# DigitalIO_3_3V_LevelShift.net
KiCad netlist of a schematic drawn in EAGLE
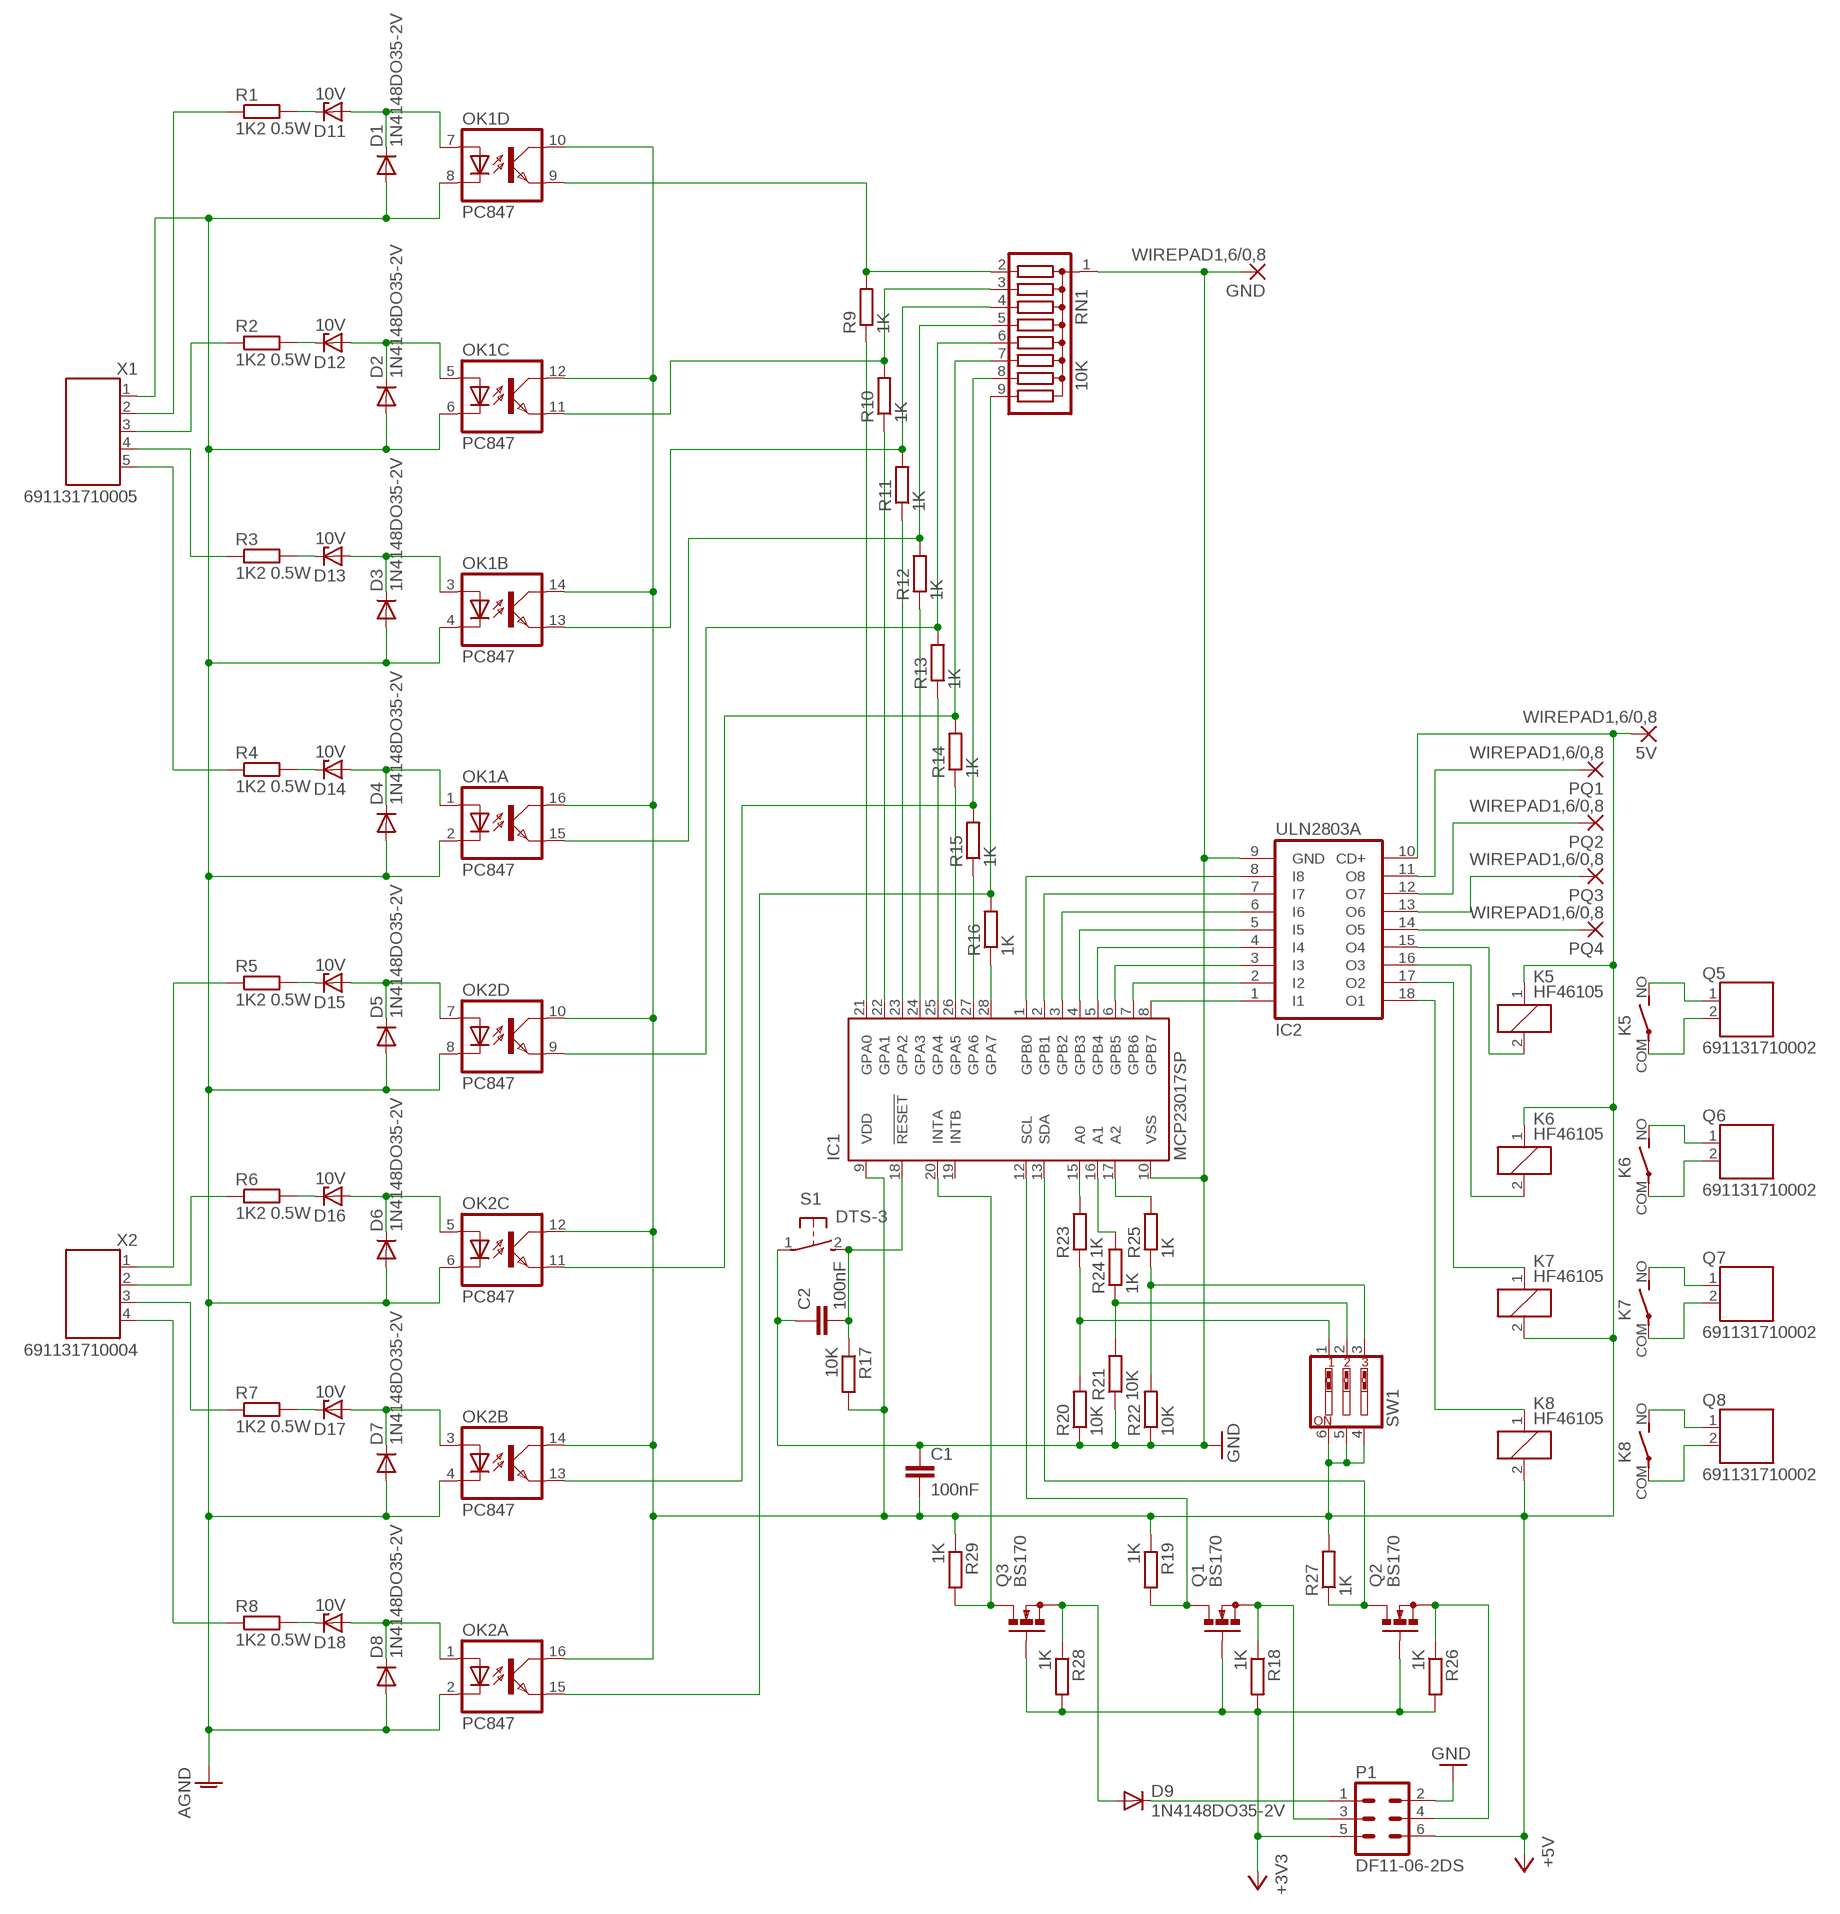
[diagram p0: schematic, sheet 1]

(export (version "E")
  (design (tool "Eeschema 10.0.6"))
  (components
    (comp (ref "5V")
      (value "WIREPAD1,6/0,8")
      (footprint "eagle-import:1,6_0,8")
      (libsource (lib "eagle-import") (part "WIREPAD1,6/0,8"))
    )
    (comp (ref "C1")
      (value "100nF")
      (footprint "eagle-import:C0805")
      (fields (field (name "MF") "MULTICOMP") (field (name "MPN") "MCRR50104X7RK0050"))
      (libsource (lib "eagle-import") (part "C-EUC0805"))
    )
    (comp (ref "C2")
      (value "100nF")
      (footprint "eagle-import:C0805")
      (fields (field (name "MF") "MULTICOMP") (field (name "MPN") "MCRR50104X7RK0050"))
      (libsource (lib "eagle-import") (part "C-EUC0805"))
    )
    (comp (ref "D1")
      (value "1N4148DO35-2V")
      (footprint "eagle-import:DO35-2V")
      (libsource (lib "eagle-import") (part "1N4148DO35-2V"))
    )
    (comp (ref "D2")
      (value "1N4148DO35-2V")
      (footprint "eagle-import:DO35-2V")
      (libsource (lib "eagle-import") (part "1N4148DO35-2V"))
    )
    (comp (ref "D3")
      (value "1N4148DO35-2V")
      (footprint "eagle-import:DO35-2V")
      (libsource (lib "eagle-import") (part "1N4148DO35-2V"))
    )
    (comp (ref "D4")
      (value "1N4148DO35-2V")
      (footprint "eagle-import:DO35-2V")
      (libsource (lib "eagle-import") (part "1N4148DO35-2V"))
    )
    (comp (ref "D5")
      (value "1N4148DO35-2V")
      (footprint "eagle-import:DO35-2V")
      (libsource (lib "eagle-import") (part "1N4148DO35-2V"))
    )
    (comp (ref "D6")
      (value "1N4148DO35-2V")
      (footprint "eagle-import:DO35-2V")
      (libsource (lib "eagle-import") (part "1N4148DO35-2V"))
    )
    (comp (ref "D7")
      (value "1N4148DO35-2V")
      (footprint "eagle-import:DO35-2V")
      (libsource (lib "eagle-import") (part "1N4148DO35-2V"))
    )
    (comp (ref "D8")
      (value "1N4148DO35-2V")
      (footprint "eagle-import:DO35-2V")
      (libsource (lib "eagle-import") (part "1N4148DO35-2V"))
    )
    (comp (ref "D9")
      (value "1N4148DO35-2V")
      (footprint "eagle-import:DO35-2V")
      (libsource (lib "eagle-import") (part "1N4148DO35-2V"))
    )
    (comp (ref "D11")
      (value "10V")
      (footprint "eagle-import:ZDIO-2.5")
      (libsource (lib "eagle-import") (part "ZENER-DIODEZD-2.5"))
    )
    (comp (ref "D12")
      (value "10V")
      (footprint "eagle-import:ZDIO-2.5")
      (libsource (lib "eagle-import") (part "ZENER-DIODEZD-2.5"))
    )
    (comp (ref "D13")
      (value "10V")
      (footprint "eagle-import:ZDIO-2.5")
      (libsource (lib "eagle-import") (part "ZENER-DIODEZD-2.5"))
    )
    (comp (ref "D14")
      (value "10V")
      (footprint "eagle-import:ZDIO-2.5")
      (libsource (lib "eagle-import") (part "ZENER-DIODEZD-2.5"))
    )
    (comp (ref "D15")
      (value "10V")
      (footprint "eagle-import:ZDIO-2.5")
      (libsource (lib "eagle-import") (part "ZENER-DIODEZD-2.5"))
    )
    (comp (ref "D16")
      (value "10V")
      (footprint "eagle-import:ZDIO-2.5")
      (libsource (lib "eagle-import") (part "ZENER-DIODEZD-2.5"))
    )
    (comp (ref "D17")
      (value "10V")
      (footprint "eagle-import:ZDIO-2.5")
      (libsource (lib "eagle-import") (part "ZENER-DIODEZD-2.5"))
    )
    (comp (ref "D18")
      (value "10V")
      (footprint "eagle-import:ZDIO-2.5")
      (libsource (lib "eagle-import") (part "ZENER-DIODEZD-2.5"))
    )
    (comp (ref "GND")
      (value "WIREPAD1,6/0,8")
      (footprint "eagle-import:1,6_0,8")
      (libsource (lib "eagle-import") (part "WIREPAD1,6/0,8"))
    )
    (comp (ref "IC1")
      (value "MCP23017SP")
      (footprint "eagle-import:DIL28-3")
      (libsource (lib "eagle-import") (part "MCP23017SP"))
    )
    (comp (ref "IC2")
      (value "ULN2803A")
      (footprint "eagle-import:DIL18")
      (fields (field (name "MF") "STMICROELECTRONICS"))
      (libsource (lib "eagle-import") (part "ULN2803A"))
    )
    (comp (ref "K5")
      (value "HF46105")
      (footprint "eagle-import:HF46")
      (libsource (lib "eagle-import") (part "HF46?105"))
    )
    (comp (ref "K6")
      (value "HF46105")
      (footprint "eagle-import:HF46")
      (libsource (lib "eagle-import") (part "HF46?105"))
    )
    (comp (ref "K7")
      (value "HF46105")
      (footprint "eagle-import:HF46")
      (libsource (lib "eagle-import") (part "HF46?105"))
    )
    (comp (ref "K8")
      (value "HF46105")
      (footprint "eagle-import:HF46")
      (libsource (lib "eagle-import") (part "HF46?105"))
    )
    (comp (ref "OK1")
      (value "PC847")
      (footprint "eagle-import:DIL16")
      (libsource (lib "eagle-import") (part "PC847"))
    )
    (comp (ref "OK2")
      (value "PC847")
      (footprint "eagle-import:DIL16")
      (libsource (lib "eagle-import") (part "PC847"))
    )
    (comp (ref "P1")
      (value "DF11-06-2DS")
      (footprint "eagle-import:DF11-06DP-2DS")
      (libsource (lib "eagle-import") (part "DF11-06-2DS"))
    )
    (comp (ref "PQ1")
      (value "WIREPAD1,6/0,8")
      (footprint "eagle-import:1,6_0,8")
      (libsource (lib "eagle-import") (part "WIREPAD1,6/0,8"))
    )
    (comp (ref "PQ2")
      (value "WIREPAD1,6/0,8")
      (footprint "eagle-import:1,6_0,8")
      (libsource (lib "eagle-import") (part "WIREPAD1,6/0,8"))
    )
    (comp (ref "PQ3")
      (value "WIREPAD1,6/0,8")
      (footprint "eagle-import:1,6_0,8")
      (libsource (lib "eagle-import") (part "WIREPAD1,6/0,8"))
    )
    (comp (ref "PQ4")
      (value "WIREPAD1,6/0,8")
      (footprint "eagle-import:1,6_0,8")
      (libsource (lib "eagle-import") (part "WIREPAD1,6/0,8"))
    )
    (comp (ref "Q1")
      (value "BS170")
      (footprint "eagle-import:SOT54E")
      (fields (field (name "MF") "ON SEMICONDUCTOR") (field (name "MPN") "BS170G"))
      (libsource (lib "eagle-import") (part "BS170"))
    )
    (comp (ref "Q2")
      (value "BS170")
      (footprint "eagle-import:SOT54E")
      (fields (field (name "MF") "ON SEMICONDUCTOR") (field (name "MPN") "BS170G"))
      (libsource (lib "eagle-import") (part "BS170"))
    )
    (comp (ref "Q3")
      (value "BS170")
      (footprint "eagle-import:SOT54E")
      (fields (field (name "MF") "ON SEMICONDUCTOR") (field (name "MPN") "BS170G"))
      (libsource (lib "eagle-import") (part "BS170"))
    )
    (comp (ref "Q5")
      (value "691131710002")
      (footprint "eagle-import:691131710002")
      (libsource (lib "eagle-import") (part "691131710002"))
    )
    (comp (ref "Q6")
      (value "691131710002")
      (footprint "eagle-import:691131710002")
      (libsource (lib "eagle-import") (part "691131710002"))
    )
    (comp (ref "Q7")
      (value "691131710002")
      (footprint "eagle-import:691131710002")
      (libsource (lib "eagle-import") (part "691131710002"))
    )
    (comp (ref "Q8")
      (value "691131710002")
      (footprint "eagle-import:691131710002")
      (libsource (lib "eagle-import") (part "691131710002"))
    )
    (comp (ref "R1")
      (value "1K2 0.5W")
      (footprint "eagle-import:0207_2V")
      (fields (field (name "MF") "MULTICOMP") (field (name "MPN") "MCF 0.25W 1K2"))
      (libsource (lib "eagle-import") (part "resistor_R-EU_0207/2V"))
    )
    (comp (ref "R2")
      (value "1K2 0.5W")
      (footprint "eagle-import:0207_2V")
      (fields (field (name "MF") "MULTICOMP") (field (name "MPN") "MCF 0.25W 1K2"))
      (libsource (lib "eagle-import") (part "resistor_R-EU_0207/2V"))
    )
    (comp (ref "R3")
      (value "1K2 0.5W")
      (footprint "eagle-import:0207_2V")
      (fields (field (name "MF") "MULTICOMP") (field (name "MPN") "MCF 0.25W 1K2"))
      (libsource (lib "eagle-import") (part "resistor_R-EU_0207/2V"))
    )
    (comp (ref "R4")
      (value "1K2 0.5W")
      (footprint "eagle-import:0207_2V")
      (fields (field (name "MF") "MULTICOMP") (field (name "MPN") "MCF 0.25W 1K2"))
      (libsource (lib "eagle-import") (part "resistor_R-EU_0207/2V"))
    )
    (comp (ref "R5")
      (value "1K2 0.5W")
      (footprint "eagle-import:0207_2V")
      (fields (field (name "MF") "MULTICOMP") (field (name "MPN") "MCF 0.25W 1K2"))
      (libsource (lib "eagle-import") (part "resistor_R-EU_0207/2V"))
    )
    (comp (ref "R6")
      (value "1K2 0.5W")
      (footprint "eagle-import:0207_2V")
      (fields (field (name "MF") "MULTICOMP") (field (name "MPN") "MCF 0.25W 1K2"))
      (libsource (lib "eagle-import") (part "resistor_R-EU_0207/2V"))
    )
    (comp (ref "R7")
      (value "1K2 0.5W")
      (footprint "eagle-import:0207_2V")
      (fields (field (name "MF") "MULTICOMP") (field (name "MPN") "MCF 0.25W 1K2"))
      (libsource (lib "eagle-import") (part "resistor_R-EU_0207/2V"))
    )
    (comp (ref "R8")
      (value "1K2 0.5W")
      (footprint "eagle-import:0207_2V")
      (fields (field (name "MF") "MULTICOMP") (field (name "MPN") "MCF 0.25W 1K2"))
      (libsource (lib "eagle-import") (part "resistor_R-EU_0207/2V"))
    )
    (comp (ref "R9")
      (value "1K")
      (footprint "eagle-import:0204V")
      (libsource (lib "eagle-import") (part "resistor_R-EU_0204/2V"))
    )
    (comp (ref "R10")
      (value "1K")
      (footprint "eagle-import:0204V")
      (libsource (lib "eagle-import") (part "resistor_R-EU_0204/2V"))
    )
    (comp (ref "R11")
      (value "1K")
      (footprint "eagle-import:0204V")
      (libsource (lib "eagle-import") (part "resistor_R-EU_0204/2V"))
    )
    (comp (ref "R12")
      (value "1K")
      (footprint "eagle-import:0204V")
      (libsource (lib "eagle-import") (part "resistor_R-EU_0204/2V"))
    )
    (comp (ref "R13")
      (value "1K")
      (footprint "eagle-import:0204V")
      (libsource (lib "eagle-import") (part "resistor_R-EU_0204/2V"))
    )
    (comp (ref "R14")
      (value "1K")
      (footprint "eagle-import:0204V")
      (libsource (lib "eagle-import") (part "resistor_R-EU_0204/2V"))
    )
    (comp (ref "R15")
      (value "1K")
      (footprint "eagle-import:0204V")
      (libsource (lib "eagle-import") (part "resistor_R-EU_0204/2V"))
    )
    (comp (ref "R16")
      (value "1K")
      (footprint "eagle-import:0204V")
      (libsource (lib "eagle-import") (part "resistor_R-EU_0204/2V"))
    )
    (comp (ref "R17")
      (value "10K")
      (footprint "eagle-import:0204V")
      (libsource (lib "eagle-import") (part "resistor_R-EU_0204/2V"))
    )
    (comp (ref "R18")
      (value "1K")
      (footprint "eagle-import:0204V")
      (libsource (lib "eagle-import") (part "R-EU_0204/2V"))
    )
    (comp (ref "R19")
      (value "1K")
      (footprint "eagle-import:0204V")
      (libsource (lib "eagle-import") (part "R-EU_0204/2V"))
    )
    (comp (ref "R20")
      (value "10K")
      (footprint "eagle-import:0204V")
      (libsource (lib "eagle-import") (part "resistor_R-EU_0204/2V"))
    )
    (comp (ref "R21")
      (value "10K")
      (footprint "eagle-import:0204V")
      (libsource (lib "eagle-import") (part "resistor_R-EU_0204/2V"))
    )
    (comp (ref "R22")
      (value "10K")
      (footprint "eagle-import:0204V")
      (libsource (lib "eagle-import") (part "resistor_R-EU_0204/2V"))
    )
    (comp (ref "R23")
      (value "1K")
      (footprint "eagle-import:0204V")
      (libsource (lib "eagle-import") (part "resistor_R-EU_0204/2V"))
    )
    (comp (ref "R24")
      (value "1K")
      (footprint "eagle-import:0204V")
      (libsource (lib "eagle-import") (part "resistor_R-EU_0204/2V"))
    )
    (comp (ref "R25")
      (value "1K")
      (footprint "eagle-import:0204V")
      (libsource (lib "eagle-import") (part "resistor_R-EU_0204/2V"))
    )
    (comp (ref "R26")
      (value "1K")
      (footprint "eagle-import:0204V")
      (libsource (lib "eagle-import") (part "R-EU_0204/2V"))
    )
    (comp (ref "R27")
      (value "1K")
      (footprint "eagle-import:0204V")
      (libsource (lib "eagle-import") (part "R-EU_0204/2V"))
    )
    (comp (ref "R28")
      (value "1K")
      (footprint "eagle-import:0204V")
      (libsource (lib "eagle-import") (part "R-EU_0204/2V"))
    )
    (comp (ref "R29")
      (value "1K")
      (footprint "eagle-import:0204V")
      (libsource (lib "eagle-import") (part "R-EU_0204/2V"))
    )
    (comp (ref "RN1")
      (value "10K")
      (footprint "eagle-import:SIL9")
      (libsource (lib "eagle-import") (part "G08R"))
    )
    (comp (ref "S1")
      (value "DTS-3")
      (footprint "eagle-import:DTS-3")
      (libsource (lib "eagle-import") (part "DTS-3"))
    )
    (comp (ref "SW1")
      (value "SW_DIP-3")
      (footprint "eagle-import:EDG-03")
      (libsource (lib "eagle-import") (part "SW_DIP-3"))
    )
    (comp (ref "X1")
      (value "691131710005")
      (footprint "eagle-import:691131710005")
      (libsource (lib "eagle-import") (part "691131710005"))
    )
    (comp (ref "X2")
      (value "691131710004")
      (footprint "eagle-import:691131710004")
      (libsource (lib "eagle-import") (part "691131710004"))
    )
  )
  (nets
    (net (code "1") (name "+3V3") (class "Default")
      (node (ref "P1") (pin "5") (pinfunction "5_5") (pintype "passive"))
      (node (ref "Q1") (pin "G") (pinfunction "G_G") (pintype "passive"))
      (node (ref "Q2") (pin "G") (pinfunction "G_G") (pintype "passive"))
      (node (ref "Q3") (pin "G") (pinfunction "G_G") (pintype "passive"))
      (node (ref "R18") (pin "2") (pinfunction "2_2") (pintype "passive"))
      (node (ref "R26") (pin "2") (pinfunction "2_2") (pintype "passive"))
      (node (ref "R28") (pin "2") (pinfunction "2_2") (pintype "passive"))
    )
    (net (code "2") (name "+5V") (class "Default")
      (node (ref "5V") (pin "1") (pinfunction "P_1") (pintype "passive"))
      (node (ref "C1") (pin "2") (pinfunction "2_2") (pintype "passive"))
      (node (ref "IC1") (pin "9") (pinfunction "VDD_9") (pintype "power_in"))
      (node (ref "IC2") (pin "10") (pinfunction "CD+_10") (pintype "passive"))
      (node (ref "K5") (pin "1") (pinfunction "1_1") (pintype "passive"))
      (node (ref "K6") (pin "1") (pinfunction "1_1") (pintype "passive"))
      (node (ref "K7") (pin "2") (pinfunction "2_2") (pintype "passive"))
      (node (ref "K8") (pin "2") (pinfunction "2_2") (pintype "passive"))
      (node (ref "OK1") (pin "10") (pinfunction "COL_10") (pintype "passive"))
      (node (ref "OK1") (pin "12") (pinfunction "COL_12") (pintype "passive"))
      (node (ref "OK1") (pin "14") (pinfunction "COL_14") (pintype "passive"))
      (node (ref "OK1") (pin "16") (pinfunction "COL_16") (pintype "passive"))
      (node (ref "OK2") (pin "10") (pinfunction "COL_10") (pintype "passive"))
      (node (ref "OK2") (pin "12") (pinfunction "COL_12") (pintype "passive"))
      (node (ref "OK2") (pin "14") (pinfunction "COL_14") (pintype "passive"))
      (node (ref "OK2") (pin "16") (pinfunction "COL_16") (pintype "passive"))
      (node (ref "P1") (pin "6") (pinfunction "6_6") (pintype "passive"))
      (node (ref "R17") (pin "2") (pinfunction "2_2") (pintype "passive"))
      (node (ref "R19") (pin "1") (pinfunction "1_1") (pintype "passive"))
      (node (ref "R27") (pin "2") (pinfunction "2_2") (pintype "passive"))
      (node (ref "R29") (pin "1") (pinfunction "1_1") (pintype "passive"))
      (node (ref "SW1") (pin "4") (pinfunction "4_4") (pintype "passive"))
      (node (ref "SW1") (pin "5") (pinfunction "5_5") (pintype "passive"))
      (node (ref "SW1") (pin "6") (pinfunction "6_6") (pintype "passive"))
    )
    (net (code "3") (name "AGND") (class "Default")
      (node (ref "D1") (pin "A") (pinfunction "A_A") (pintype "passive"))
      (node (ref "D2") (pin "A") (pinfunction "A_A") (pintype "passive"))
      (node (ref "D3") (pin "A") (pinfunction "A_A") (pintype "passive"))
      (node (ref "D4") (pin "A") (pinfunction "A_A") (pintype "passive"))
      (node (ref "D5") (pin "A") (pinfunction "A_A") (pintype "passive"))
      (node (ref "D6") (pin "A") (pinfunction "A_A") (pintype "passive"))
      (node (ref "D7") (pin "A") (pinfunction "A_A") (pintype "passive"))
      (node (ref "D8") (pin "A") (pinfunction "A_A") (pintype "passive"))
      (node (ref "OK1") (pin "2") (pinfunction "C_2") (pintype "passive"))
      (node (ref "OK1") (pin "4") (pinfunction "C_4") (pintype "passive"))
      (node (ref "OK1") (pin "6") (pinfunction "C_6") (pintype "passive"))
      (node (ref "OK1") (pin "8") (pinfunction "C_8") (pintype "passive"))
      (node (ref "OK2") (pin "2") (pinfunction "C_2") (pintype "passive"))
      (node (ref "OK2") (pin "4") (pinfunction "C_4") (pintype "passive"))
      (node (ref "OK2") (pin "6") (pinfunction "C_6") (pintype "passive"))
      (node (ref "OK2") (pin "8") (pinfunction "C_8") (pintype "passive"))
      (node (ref "X1") (pin "1") (pinfunction "1_1") (pintype "passive"))
    )
    (net (code "4") (name "GND") (class "Default")
      (node (ref "C1") (pin "1") (pinfunction "1_1") (pintype "passive"))
      (node (ref "C2") (pin "1") (pinfunction "1_1") (pintype "passive"))
      (node (ref "GND") (pin "1") (pinfunction "P_1") (pintype "passive"))
      (node (ref "IC1") (pin "10") (pinfunction "VSS_10") (pintype "power_in"))
      (node (ref "IC2") (pin "9") (pinfunction "GND_9") (pintype "power_in"))
      (node (ref "P1") (pin "2") (pinfunction "2_2") (pintype "passive"))
      (node (ref "R20") (pin "1") (pinfunction "1_1") (pintype "passive"))
      (node (ref "R21") (pin "1") (pinfunction "1_1") (pintype "passive"))
      (node (ref "R22") (pin "1") (pinfunction "1_1") (pintype "passive"))
      (node (ref "RN1") (pin "1") (pinfunction "1_1") (pintype "passive"))
      (node (ref "S1") (pin "1") (pinfunction "1_1") (pintype "passive"))
    )
    (net (code "5") (name "Net-(D9-PadA)") (class "Default")
      (node (ref "D9") (pin "A") (pinfunction "A_A") (pintype "passive"))
      (node (ref "Q3") (pin "S") (pinfunction "S_S") (pintype "passive"))
      (node (ref "R28") (pin "1") (pinfunction "1_1") (pintype "passive"))
    )
    (net (code "6") (name "Net-(D9-PadC)") (class "Default")
      (node (ref "D9") (pin "C") (pinfunction "C_C") (pintype "passive"))
      (node (ref "P1") (pin "1") (pinfunction "1_1") (pintype "passive"))
    )
    (net (code "7") (name "Net-(D11-PadC)") (class "Default")
      (node (ref "D11") (pin "C") (pinfunction "C_C") (pintype "passive"))
      (node (ref "R1") (pin "2") (pinfunction "2_2") (pintype "passive"))
    )
    (net (code "8") (name "Net-(D12-PadC)") (class "Default")
      (node (ref "D12") (pin "C") (pinfunction "C_C") (pintype "passive"))
      (node (ref "R2") (pin "2") (pinfunction "2_2") (pintype "passive"))
    )
    (net (code "9") (name "Net-(D13-PadC)") (class "Default")
      (node (ref "D13") (pin "C") (pinfunction "C_C") (pintype "passive"))
      (node (ref "R3") (pin "2") (pinfunction "2_2") (pintype "passive"))
    )
    (net (code "10") (name "Net-(D14-PadC)") (class "Default")
      (node (ref "D14") (pin "C") (pinfunction "C_C") (pintype "passive"))
      (node (ref "R4") (pin "2") (pinfunction "2_2") (pintype "passive"))
    )
    (net (code "11") (name "Net-(D15-PadC)") (class "Default")
      (node (ref "D15") (pin "C") (pinfunction "C_C") (pintype "passive"))
      (node (ref "R5") (pin "2") (pinfunction "2_2") (pintype "passive"))
    )
    (net (code "12") (name "Net-(D16-PadC)") (class "Default")
      (node (ref "D16") (pin "C") (pinfunction "C_C") (pintype "passive"))
      (node (ref "R6") (pin "2") (pinfunction "2_2") (pintype "passive"))
    )
    (net (code "13") (name "Net-(D17-PadC)") (class "Default")
      (node (ref "D17") (pin "C") (pinfunction "C_C") (pintype "passive"))
      (node (ref "R7") (pin "2") (pinfunction "2_2") (pintype "passive"))
    )
    (net (code "14") (name "Net-(D18-PadC)") (class "Default")
      (node (ref "D18") (pin "C") (pinfunction "C_C") (pintype "passive"))
      (node (ref "R8") (pin "2") (pinfunction "2_2") (pintype "passive"))
    )
    (net (code "15") (name "Net-(IC1-A0)") (class "Default")
      (node (ref "IC1") (pin "15") (pinfunction "A0_15") (pintype "input"))
      (node (ref "R23") (pin "2") (pinfunction "2_2") (pintype "passive"))
    )
    (net (code "16") (name "Net-(IC1-A1)") (class "Default")
      (node (ref "IC1") (pin "16") (pinfunction "A1_16") (pintype "input"))
      (node (ref "R24") (pin "2") (pinfunction "2_2") (pintype "passive"))
    )
    (net (code "17") (name "Net-(IC1-A2)") (class "Default")
      (node (ref "IC1") (pin "17") (pinfunction "A2_17") (pintype "input"))
      (node (ref "R25") (pin "2") (pinfunction "2_2") (pintype "passive"))
    )
    (net (code "18") (name "Net-(IC1-GPA0)") (class "Default")
      (node (ref "IC1") (pin "21") (pinfunction "GPA0_21") (pintype "bidirectional"))
      (node (ref "R9") (pin "1") (pinfunction "1_1") (pintype "passive"))
    )
    (net (code "19") (name "Net-(IC1-GPA1)") (class "Default")
      (node (ref "IC1") (pin "22") (pinfunction "GPA1_22") (pintype "bidirectional"))
      (node (ref "R10") (pin "1") (pinfunction "1_1") (pintype "passive"))
    )
    (net (code "20") (name "Net-(IC1-GPA2)") (class "Default")
      (node (ref "IC1") (pin "23") (pinfunction "GPA2_23") (pintype "bidirectional"))
      (node (ref "R11") (pin "1") (pinfunction "1_1") (pintype "passive"))
    )
    (net (code "21") (name "Net-(IC1-GPA3)") (class "Default")
      (node (ref "IC1") (pin "24") (pinfunction "GPA3_24") (pintype "bidirectional"))
      (node (ref "R12") (pin "1") (pinfunction "1_1") (pintype "passive"))
    )
    (net (code "22") (name "Net-(IC1-GPA4)") (class "Default")
      (node (ref "IC1") (pin "25") (pinfunction "GPA4_25") (pintype "bidirectional"))
      (node (ref "R13") (pin "1") (pinfunction "1_1") (pintype "passive"))
    )
    (net (code "23") (name "Net-(IC1-GPA5)") (class "Default")
      (node (ref "IC1") (pin "26") (pinfunction "GPA5_26") (pintype "bidirectional"))
      (node (ref "R14") (pin "1") (pinfunction "1_1") (pintype "passive"))
    )
    (net (code "24") (name "Net-(IC1-GPA6)") (class "Default")
      (node (ref "IC1") (pin "27") (pinfunction "GPA6_27") (pintype "bidirectional"))
      (node (ref "R15") (pin "1") (pinfunction "1_1") (pintype "passive"))
    )
    (net (code "25") (name "Net-(IC1-GPA7)") (class "Default")
      (node (ref "IC1") (pin "28") (pinfunction "GPA7_28") (pintype "bidirectional"))
      (node (ref "R16") (pin "1") (pinfunction "1_1") (pintype "passive"))
    )
    (net (code "26") (name "Net-(IC1-GPB0)") (class "Default")
      (node (ref "IC1") (pin "1") (pinfunction "GPB0_1") (pintype "bidirectional"))
      (node (ref "IC2") (pin "8") (pinfunction "I8_8") (pintype "input"))
    )
    (net (code "27") (name "Net-(IC1-GPB1)") (class "Default")
      (node (ref "IC1") (pin "2") (pinfunction "GPB1_2") (pintype "bidirectional"))
      (node (ref "IC2") (pin "7") (pinfunction "I7_7") (pintype "input"))
    )
    (net (code "28") (name "Net-(IC1-GPB2)") (class "Default")
      (node (ref "IC1") (pin "3") (pinfunction "GPB2_3") (pintype "bidirectional"))
      (node (ref "IC2") (pin "6") (pinfunction "I6_6") (pintype "input"))
    )
    (net (code "29") (name "Net-(IC1-GPB3)") (class "Default")
      (node (ref "IC1") (pin "4") (pinfunction "GPB3_4") (pintype "bidirectional"))
      (node (ref "IC2") (pin "5") (pinfunction "I5_5") (pintype "input"))
    )
    (net (code "30") (name "Net-(IC1-GPB4)") (class "Default")
      (node (ref "IC1") (pin "5") (pinfunction "GPB4_5") (pintype "bidirectional"))
      (node (ref "IC2") (pin "4") (pinfunction "I4_4") (pintype "input"))
    )
    (net (code "31") (name "Net-(IC1-GPB5)") (class "Default")
      (node (ref "IC1") (pin "6") (pinfunction "GPB5_6") (pintype "bidirectional"))
      (node (ref "IC2") (pin "3") (pinfunction "I3_3") (pintype "input"))
    )
    (net (code "32") (name "Net-(IC1-GPB6)") (class "Default")
      (node (ref "IC1") (pin "7") (pinfunction "GPB6_7") (pintype "bidirectional"))
      (node (ref "IC2") (pin "2") (pinfunction "I2_2") (pintype "input"))
    )
    (net (code "33") (name "Net-(IC1-GPB7)") (class "Default")
      (node (ref "IC1") (pin "8") (pinfunction "GPB7_8") (pintype "bidirectional"))
      (node (ref "IC2") (pin "1") (pinfunction "I1_1") (pintype "input"))
    )
    (net (code "34") (name "Net-(IC1-INTA)") (class "Default")
      (node (ref "IC1") (pin "20") (pinfunction "INTA_20") (pintype "output"))
      (node (ref "Q3") (pin "D") (pinfunction "D_D") (pintype "passive"))
      (node (ref "R29") (pin "2") (pinfunction "2_2") (pintype "passive"))
    )
    (net (code "35") (name "Net-(IC1-SCL)") (class "Default")
      (node (ref "IC1") (pin "12") (pinfunction "SCL_12") (pintype "input"))
      (node (ref "Q1") (pin "D") (pinfunction "D_D") (pintype "passive"))
      (node (ref "R19") (pin "2") (pinfunction "2_2") (pintype "passive"))
    )
    (net (code "36") (name "Net-(IC1-SDA)") (class "Default")
      (node (ref "IC1") (pin "13") (pinfunction "SDA_13") (pintype "bidirectional"))
      (node (ref "Q2") (pin "D") (pinfunction "D_D") (pintype "passive"))
      (node (ref "R27") (pin "1") (pinfunction "1_1") (pintype "passive"))
    )
    (net (code "37") (name "Net-(IC1-~{RESET})") (class "Default")
      (node (ref "C2") (pin "2") (pinfunction "2_2") (pintype "passive"))
      (node (ref "IC1") (pin "18") (pinfunction "~{RESET}_18") (pintype "input"))
      (node (ref "R17") (pin "1") (pinfunction "1_1") (pintype "passive"))
      (node (ref "S1") (pin "2") (pinfunction "2_2") (pintype "passive"))
    )
    (net (code "38") (name "Net-(IC2-O1)") (class "Default")
      (node (ref "IC2") (pin "18") (pinfunction "O1_18") (pintype "open_collector"))
      (node (ref "K8") (pin "1") (pinfunction "1_1") (pintype "passive"))
    )
    (net (code "39") (name "Net-(IC2-O2)") (class "Default")
      (node (ref "IC2") (pin "17") (pinfunction "O2_17") (pintype "open_collector"))
      (node (ref "K7") (pin "1") (pinfunction "1_1") (pintype "passive"))
    )
    (net (code "40") (name "Net-(IC2-O3)") (class "Default")
      (node (ref "IC2") (pin "16") (pinfunction "O3_16") (pintype "open_collector"))
      (node (ref "K6") (pin "2") (pinfunction "2_2") (pintype "passive"))
    )
    (net (code "41") (name "Net-(IC2-O4)") (class "Default")
      (node (ref "IC2") (pin "15") (pinfunction "O4_15") (pintype "open_collector"))
      (node (ref "K5") (pin "2") (pinfunction "2_2") (pintype "passive"))
    )
    (net (code "42") (name "Net-(IC2-O5)") (class "Default")
      (node (ref "IC2") (pin "14") (pinfunction "O5_14") (pintype "open_collector"))
      (node (ref "PQ4") (pin "1") (pinfunction "P_1") (pintype "passive"))
    )
    (net (code "43") (name "Net-(IC2-O6)") (class "Default")
      (node (ref "IC2") (pin "13") (pinfunction "O6_13") (pintype "open_collector"))
      (node (ref "PQ3") (pin "1") (pinfunction "P_1") (pintype "passive"))
    )
    (net (code "44") (name "Net-(IC2-O7)") (class "Default")
      (node (ref "IC2") (pin "12") (pinfunction "O7_12") (pintype "open_collector"))
      (node (ref "PQ2") (pin "1") (pinfunction "P_1") (pintype "passive"))
    )
    (net (code "45") (name "Net-(IC2-O8)") (class "Default")
      (node (ref "IC2") (pin "11") (pinfunction "O8_11") (pintype "open_collector"))
      (node (ref "PQ1") (pin "1") (pinfunction "P_1") (pintype "passive"))
    )
    (net (code "46") (name "Net-(K5B-P)") (class "Default")
      (node (ref "K5") (pin "COM") (pinfunction "P_COM") (pintype "passive"))
      (node (ref "Q5") (pin "2") (pinfunction "2_2") (pintype "passive"))
    )
    (net (code "47") (name "Net-(K5B-S)") (class "Default")
      (node (ref "K5") (pin "NO") (pinfunction "S_NO") (pintype "passive"))
      (node (ref "Q5") (pin "1") (pinfunction "1_1") (pintype "passive"))
    )
    (net (code "48") (name "Net-(K6B-P)") (class "Default")
      (node (ref "K6") (pin "COM") (pinfunction "P_COM") (pintype "passive"))
      (node (ref "Q6") (pin "2") (pinfunction "2_2") (pintype "passive"))
    )
    (net (code "49") (name "Net-(K6B-S)") (class "Default")
      (node (ref "K6") (pin "NO") (pinfunction "S_NO") (pintype "passive"))
      (node (ref "Q6") (pin "1") (pinfunction "1_1") (pintype "passive"))
    )
    (net (code "50") (name "Net-(K7B-P)") (class "Default")
      (node (ref "K7") (pin "COM") (pinfunction "P_COM") (pintype "passive"))
      (node (ref "Q7") (pin "2") (pinfunction "2_2") (pintype "passive"))
    )
    (net (code "51") (name "Net-(K7B-S)") (class "Default")
      (node (ref "K7") (pin "NO") (pinfunction "S_NO") (pintype "passive"))
      (node (ref "Q7") (pin "1") (pinfunction "1_1") (pintype "passive"))
    )
    (net (code "52") (name "Net-(K8B-P)") (class "Default")
      (node (ref "K8") (pin "COM") (pinfunction "P_COM") (pintype "passive"))
      (node (ref "Q8") (pin "2") (pinfunction "2_2") (pintype "passive"))
    )
    (net (code "53") (name "Net-(K8B-S)") (class "Default")
      (node (ref "K8") (pin "NO") (pinfunction "S_NO") (pintype "passive"))
      (node (ref "Q8") (pin "1") (pinfunction "1_1") (pintype "passive"))
    )
    (net (code "54") (name "Net-(OK1A-A)") (class "Default")
      (node (ref "D14") (pin "A") (pinfunction "A_A") (pintype "passive"))
      (node (ref "D4") (pin "C") (pinfunction "C_C") (pintype "passive"))
      (node (ref "OK1") (pin "1") (pinfunction "A_1") (pintype "passive"))
    )
    (net (code "55") (name "Net-(OK1A-EMIT)") (class "Default")
      (node (ref "OK1") (pin "15") (pinfunction "EMIT_15") (pintype "passive"))
      (node (ref "R12") (pin "2") (pinfunction "2_2") (pintype "passive"))
      (node (ref "RN1") (pin "5") (pinfunction "5_5") (pintype "passive"))
    )
    (net (code "56") (name "Net-(OK1B-A)") (class "Default")
      (node (ref "D13") (pin "A") (pinfunction "A_A") (pintype "passive"))
      (node (ref "D3") (pin "C") (pinfunction "C_C") (pintype "passive"))
      (node (ref "OK1") (pin "3") (pinfunction "A_3") (pintype "passive"))
    )
    (net (code "57") (name "Net-(OK1B-EMIT)") (class "Default")
      (node (ref "OK1") (pin "13") (pinfunction "EMIT_13") (pintype "passive"))
      (node (ref "R11") (pin "2") (pinfunction "2_2") (pintype "passive"))
      (node (ref "RN1") (pin "4") (pinfunction "4_4") (pintype "passive"))
    )
    (net (code "58") (name "Net-(OK1C-A)") (class "Default")
      (node (ref "D12") (pin "A") (pinfunction "A_A") (pintype "passive"))
      (node (ref "D2") (pin "C") (pinfunction "C_C") (pintype "passive"))
      (node (ref "OK1") (pin "5") (pinfunction "A_5") (pintype "passive"))
    )
    (net (code "59") (name "Net-(OK1C-EMIT)") (class "Default")
      (node (ref "OK1") (pin "11") (pinfunction "EMIT_11") (pintype "passive"))
      (node (ref "R10") (pin "2") (pinfunction "2_2") (pintype "passive"))
      (node (ref "RN1") (pin "3") (pinfunction "3_3") (pintype "passive"))
    )
    (net (code "60") (name "Net-(OK1D-A)") (class "Default")
      (node (ref "D1") (pin "C") (pinfunction "C_C") (pintype "passive"))
      (node (ref "D11") (pin "A") (pinfunction "A_A") (pintype "passive"))
      (node (ref "OK1") (pin "7") (pinfunction "A_7") (pintype "passive"))
    )
    (net (code "61") (name "Net-(OK1D-EMIT)") (class "Default")
      (node (ref "OK1") (pin "9") (pinfunction "EMIT_9") (pintype "passive"))
      (node (ref "R9") (pin "2") (pinfunction "2_2") (pintype "passive"))
      (node (ref "RN1") (pin "2") (pinfunction "2_2") (pintype "passive"))
    )
    (net (code "62") (name "Net-(OK2A-A)") (class "Default")
      (node (ref "D18") (pin "A") (pinfunction "A_A") (pintype "passive"))
      (node (ref "D8") (pin "C") (pinfunction "C_C") (pintype "passive"))
      (node (ref "OK2") (pin "1") (pinfunction "A_1") (pintype "passive"))
    )
    (net (code "63") (name "Net-(OK2A-EMIT)") (class "Default")
      (node (ref "OK2") (pin "15") (pinfunction "EMIT_15") (pintype "passive"))
      (node (ref "R16") (pin "2") (pinfunction "2_2") (pintype "passive"))
      (node (ref "RN1") (pin "9") (pinfunction "9_9") (pintype "passive"))
    )
    (net (code "64") (name "Net-(OK2B-A)") (class "Default")
      (node (ref "D17") (pin "A") (pinfunction "A_A") (pintype "passive"))
      (node (ref "D7") (pin "C") (pinfunction "C_C") (pintype "passive"))
      (node (ref "OK2") (pin "3") (pinfunction "A_3") (pintype "passive"))
    )
    (net (code "65") (name "Net-(OK2B-EMIT)") (class "Default")
      (node (ref "OK2") (pin "13") (pinfunction "EMIT_13") (pintype "passive"))
      (node (ref "R15") (pin "2") (pinfunction "2_2") (pintype "passive"))
      (node (ref "RN1") (pin "8") (pinfunction "8_8") (pintype "passive"))
    )
    (net (code "66") (name "Net-(OK2C-A)") (class "Default")
      (node (ref "D16") (pin "A") (pinfunction "A_A") (pintype "passive"))
      (node (ref "D6") (pin "C") (pinfunction "C_C") (pintype "passive"))
      (node (ref "OK2") (pin "5") (pinfunction "A_5") (pintype "passive"))
    )
    (net (code "67") (name "Net-(OK2C-EMIT)") (class "Default")
      (node (ref "OK2") (pin "11") (pinfunction "EMIT_11") (pintype "passive"))
      (node (ref "R14") (pin "2") (pinfunction "2_2") (pintype "passive"))
      (node (ref "RN1") (pin "7") (pinfunction "7_7") (pintype "passive"))
    )
    (net (code "68") (name "Net-(OK2D-A)") (class "Default")
      (node (ref "D15") (pin "A") (pinfunction "A_A") (pintype "passive"))
      (node (ref "D5") (pin "C") (pinfunction "C_C") (pintype "passive"))
      (node (ref "OK2") (pin "7") (pinfunction "A_7") (pintype "passive"))
    )
    (net (code "69") (name "Net-(OK2D-EMIT)") (class "Default")
      (node (ref "OK2") (pin "9") (pinfunction "EMIT_9") (pintype "passive"))
      (node (ref "R13") (pin "2") (pinfunction "2_2") (pintype "passive"))
      (node (ref "RN1") (pin "6") (pinfunction "6_6") (pintype "passive"))
    )
    (net (code "70") (name "Net-(P1-Pad3)") (class "Default")
      (node (ref "P1") (pin "3") (pinfunction "3_3") (pintype "passive"))
      (node (ref "Q1") (pin "S") (pinfunction "S_S") (pintype "passive"))
      (node (ref "R18") (pin "1") (pinfunction "1_1") (pintype "passive"))
    )
    (net (code "71") (name "Net-(P1-Pad4)") (class "Default")
      (node (ref "P1") (pin "4") (pinfunction "4_4") (pintype "passive"))
      (node (ref "Q2") (pin "S") (pinfunction "S_S") (pintype "passive"))
      (node (ref "R26") (pin "1") (pinfunction "1_1") (pintype "passive"))
    )
    (net (code "72") (name "Net-(R1-Pad1)") (class "Default")
      (node (ref "R1") (pin "1") (pinfunction "1_1") (pintype "passive"))
      (node (ref "X1") (pin "2") (pinfunction "2_2") (pintype "passive"))
    )
    (net (code "73") (name "Net-(R2-Pad1)") (class "Default")
      (node (ref "R2") (pin "1") (pinfunction "1_1") (pintype "passive"))
      (node (ref "X1") (pin "3") (pinfunction "3_3") (pintype "passive"))
    )
    (net (code "74") (name "Net-(R3-Pad1)") (class "Default")
      (node (ref "R3") (pin "1") (pinfunction "1_1") (pintype "passive"))
      (node (ref "X1") (pin "4") (pinfunction "4_4") (pintype "passive"))
    )
    (net (code "75") (name "Net-(R4-Pad1)") (class "Default")
      (node (ref "R4") (pin "1") (pinfunction "1_1") (pintype "passive"))
      (node (ref "X1") (pin "5") (pinfunction "5_5") (pintype "passive"))
    )
    (net (code "76") (name "Net-(R5-Pad1)") (class "Default")
      (node (ref "R5") (pin "1") (pinfunction "1_1") (pintype "passive"))
      (node (ref "X2") (pin "1") (pinfunction "1_1") (pintype "passive"))
    )
    (net (code "77") (name "Net-(R6-Pad1)") (class "Default")
      (node (ref "R6") (pin "1") (pinfunction "1_1") (pintype "passive"))
      (node (ref "X2") (pin "2") (pinfunction "2_2") (pintype "passive"))
    )
    (net (code "78") (name "Net-(R7-Pad1)") (class "Default")
      (node (ref "R7") (pin "1") (pinfunction "1_1") (pintype "passive"))
      (node (ref "X2") (pin "3") (pinfunction "3_3") (pintype "passive"))
    )
    (net (code "79") (name "Net-(R8-Pad1)") (class "Default")
      (node (ref "R8") (pin "1") (pinfunction "1_1") (pintype "passive"))
      (node (ref "X2") (pin "4") (pinfunction "4_4") (pintype "passive"))
    )
    (net (code "80") (name "Net-(R20-Pad2)") (class "Default")
      (node (ref "R20") (pin "2") (pinfunction "2_2") (pintype "passive"))
      (node (ref "R23") (pin "1") (pinfunction "1_1") (pintype "passive"))
      (node (ref "SW1") (pin "1") (pinfunction "1_1") (pintype "passive"))
    )
    (net (code "81") (name "Net-(R21-Pad2)") (class "Default")
      (node (ref "R21") (pin "2") (pinfunction "2_2") (pintype "passive"))
      (node (ref "R24") (pin "1") (pinfunction "1_1") (pintype "passive"))
      (node (ref "SW1") (pin "2") (pinfunction "2_2") (pintype "passive"))
    )
    (net (code "82") (name "Net-(R22-Pad2)") (class "Default")
      (node (ref "R22") (pin "2") (pinfunction "2_2") (pintype "passive"))
      (node (ref "R25") (pin "1") (pinfunction "1_1") (pintype "passive"))
      (node (ref "SW1") (pin "3") (pinfunction "3_3") (pintype "passive"))
    )
    (net (code "83") (name "unconnected-(IC1-INTB-Pad19)") (class "Default")
      (node (ref "IC1") (pin "19") (pinfunction "INTB_19") (pintype "output"))
    )
  )
)
